# PAGE1.net
KiCad netlist of a schematic drawn in Altium Designer
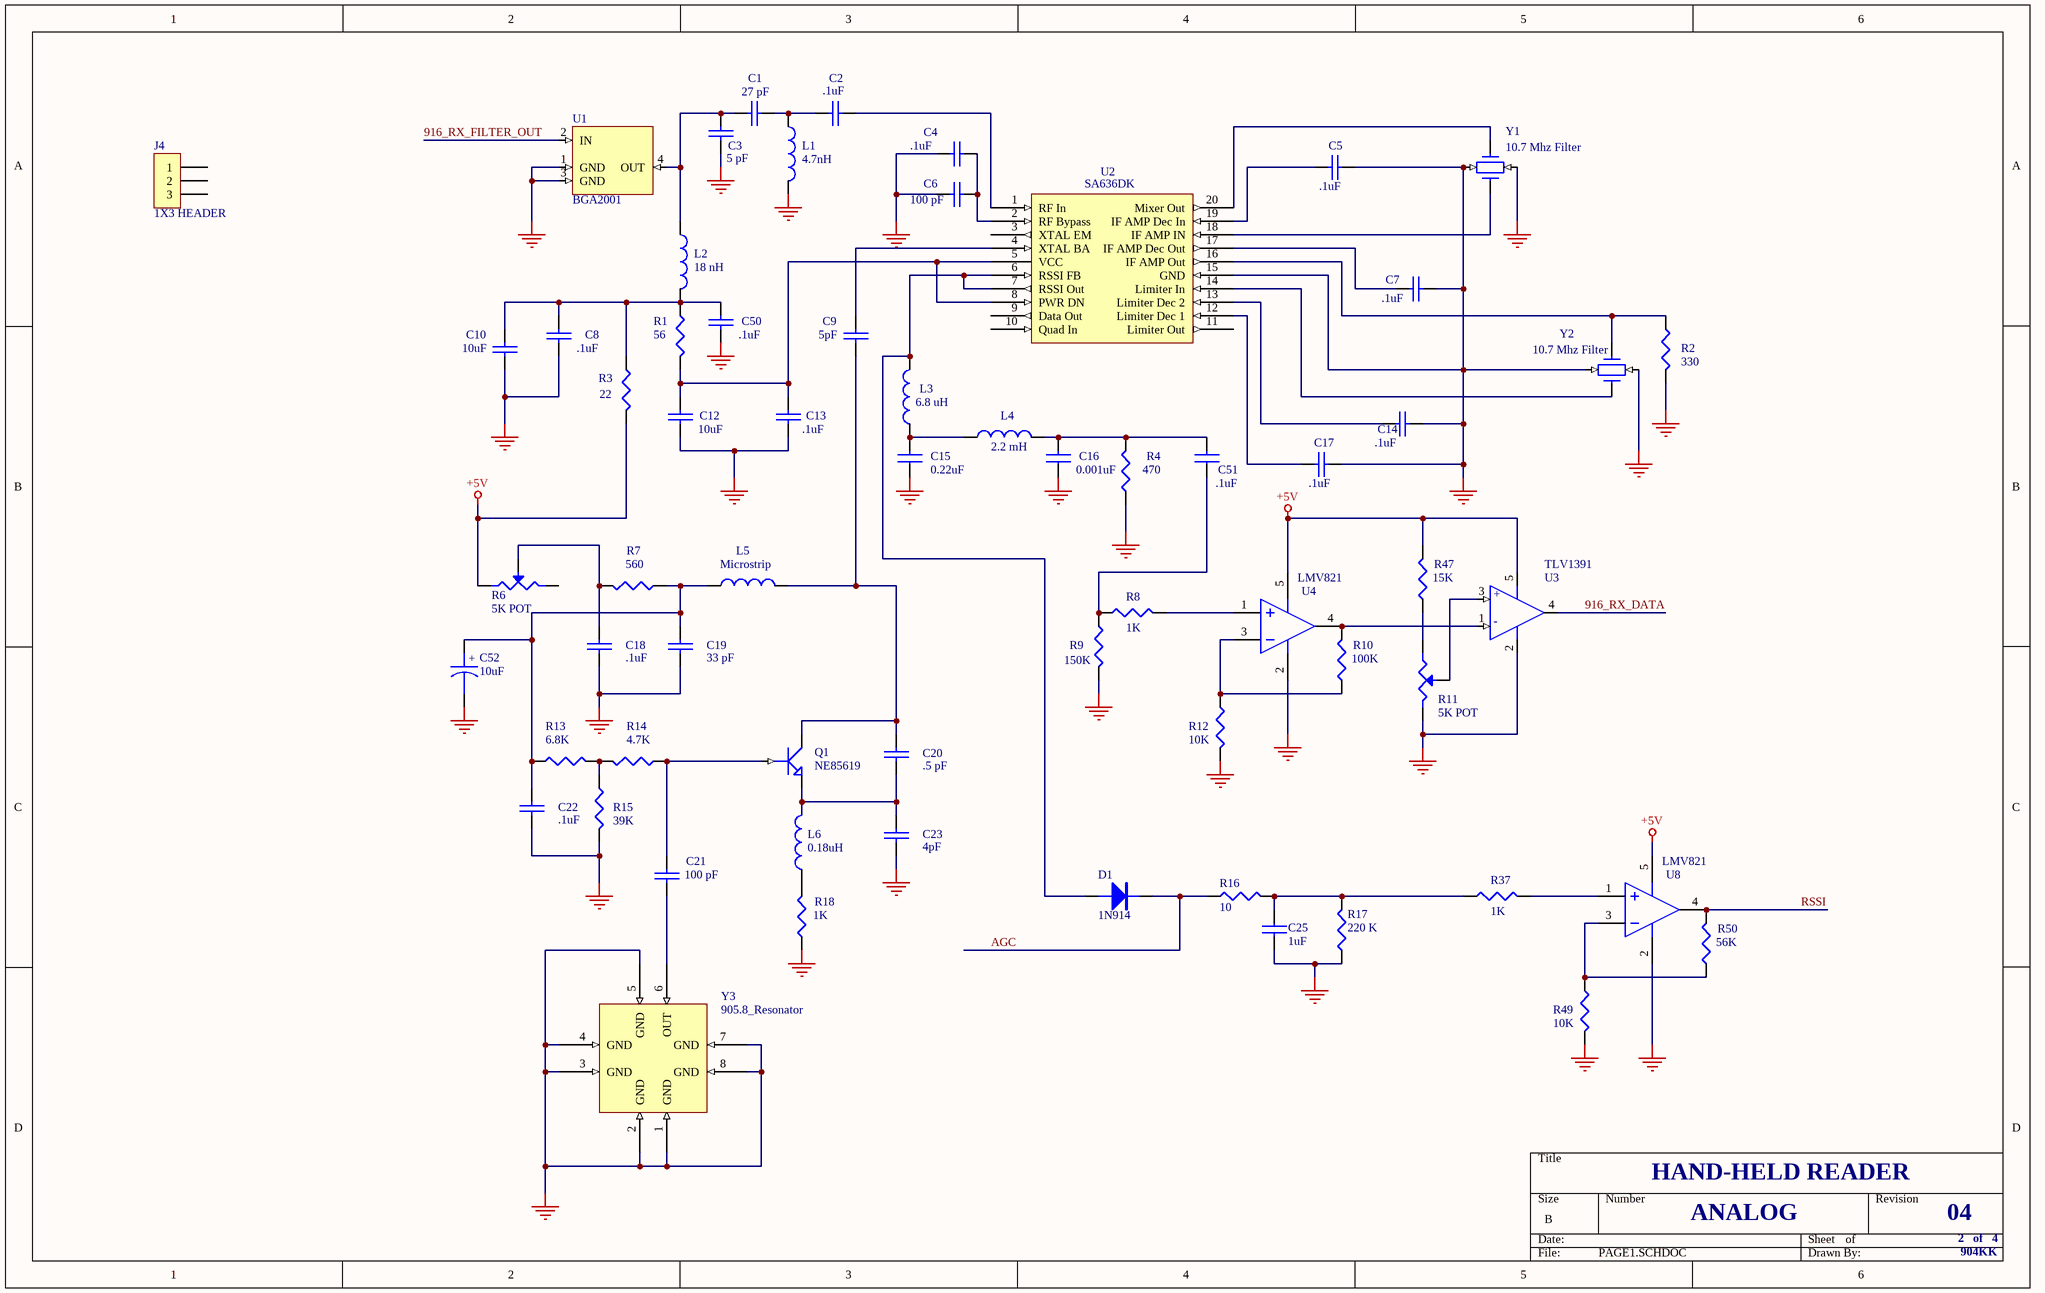
[diagram p0: PAGE1.SCHDOC]

(export (version "E")
  (design (tool "Eeschema 10.0.6"))
  (components
    (comp (ref "C1")
      (value "27 pF")
      (footprint "0603")
      (description "Capacitor")
      (libsource (lib "*") (part "CAP"))
    )
    (comp (ref "C2")
      (value ".1uF")
      (footprint "0603")
      (description "Capacitor")
      (libsource (lib "*") (part "CAP"))
    )
    (comp (ref "C3")
      (value "5 pF")
      (footprint "0603")
      (description "Capacitor")
      (libsource (lib "*") (part "CAP"))
    )
    (comp (ref "C4")
      (value ".1uF")
      (footprint "0603")
      (description "Capacitor")
      (libsource (lib "*") (part "CAP"))
    )
    (comp (ref "C5")
      (value ".1uF")
      (footprint "0603")
      (description "Capacitor")
      (libsource (lib "*") (part "CAP"))
    )
    (comp (ref "C6")
      (value "100 pF")
      (footprint "0603")
      (description "Capacitor")
      (libsource (lib "*") (part "CAP"))
    )
    (comp (ref "C7")
      (value ".1uF")
      (footprint "0603")
      (description "Capacitor")
      (libsource (lib "*") (part "CAP"))
    )
    (comp (ref "C8")
      (value ".1uF")
      (footprint "0603")
      (description "Capacitor")
      (libsource (lib "*") (part "CAP"))
    )
    (comp (ref "C9")
      (value "5pF")
      (footprint "0603")
      (description "Capacitor")
      (libsource (lib "*") (part "CAP"))
    )
    (comp (ref "C10")
      (value "10uF")
      (footprint "CAP A CASE")
      (description "Capacitor")
      (libsource (lib "*") (part "CAP"))
    )
    (comp (ref "C12")
      (value "10uF")
      (footprint "CAP A CASE")
      (description "Capacitor")
      (libsource (lib "*") (part "CAP"))
    )
    (comp (ref "C13")
      (value ".1uF")
      (footprint "0603")
      (description "Capacitor")
      (libsource (lib "*") (part "CAP"))
    )
    (comp (ref "C14")
      (value ".1uF")
      (footprint "0603")
      (description "Capacitor")
      (libsource (lib "*") (part "CAP"))
    )
    (comp (ref "C15") (value "0.22uF") (footprint "0603") (libsource (lib "*") (part "CAP_NP")))
    (comp (ref "C16") (value "0.001uF") (footprint "0603") (libsource (lib "*") (part "CAP_NP")))
    (comp (ref "C17")
      (value ".1uF")
      (footprint "0603")
      (description "Capacitor")
      (libsource (lib "*") (part "CAP"))
    )
    (comp (ref "C18")
      (value ".1uF")
      (footprint "0603")
      (description "Capacitor")
      (libsource (lib "*") (part "CAP"))
    )
    (comp (ref "C19")
      (value "33 pF")
      (footprint "0603")
      (description "Capacitor")
      (libsource (lib "*") (part "CAP"))
    )
    (comp (ref "C20")
      (value ".5 pF")
      (footprint "0603")
      (description "Capacitor")
      (libsource (lib "*") (part "CAP"))
    )
    (comp (ref "C21")
      (value "100 pF")
      (footprint "0603")
      (description "Capacitor")
      (libsource (lib "*") (part "CAP"))
    )
    (comp (ref "C22")
      (value ".1uF")
      (footprint "0603")
      (description "Capacitor")
      (libsource (lib "*") (part "CAP"))
    )
    (comp (ref "C23")
      (value "4pF")
      (footprint "0603")
      (description "Capacitor")
      (libsource (lib "*") (part "CAP"))
    )
    (comp (ref "C25") (value "1uF") (footprint "CAP A CASE") (libsource (lib "*") (part "CAP_NP")))
    (comp (ref "C50")
      (value ".1uF")
      (footprint "0603")
      (description "Capacitor")
      (libsource (lib "*") (part "CAP"))
    )
    (comp (ref "C51") (value ".1uF") (footprint "0603") (libsource (lib "*") (part "CAP_NP")))
    (comp (ref "C52")
      (value "10uF")
      (footprint "CAP A CASE")
      (description "Capacitor")
      (libsource (lib "*") (part "CAPACITOR POL"))
    )
    (comp (ref "D1")
      (value "1N914")
      (footprint "SOT23 DIODE")
      (description "Diode")
      (libsource (lib "*") (part "DIODE"))
    )
    (comp (ref "J4")
      (value "1X3 HEADER")
      (footprint "1X3 HEADER")
      (description "Connector")
      (libsource (lib "*") (part "CON3"))
    )
    (comp (ref "L1") (value "4.7nH") (footprint "0603") (libsource (lib "*") (part "INDUCTOR")))
    (comp (ref "L2") (value "18 nH") (footprint "0603") (libsource (lib "*") (part "INDUCTOR")))
    (comp (ref "L3") (value "6.8 uH") (footprint "0805") (libsource (lib "*") (part "INDUCTOR")))
    (comp (ref "L4") (value "2.2 mH") (footprint "COIL 6.8UH") (libsource (lib "*") (part "INDUCTOR")))
    (comp (ref "L5") (value "Microstrip") (footprint "MICROSTRIP") (libsource (lib "*") (part "INDUCTOR")))
    (comp (ref "L6") (value "0.18uH") (footprint "0603") (libsource (lib "*") (part "INDUCTOR")))
    (comp (ref "Q1")
      (value "NE85619")
      (footprint "3 PIN ULTRA SUPER MINI MOLD")
      (description "NPN Transistor")
      (libsource (lib "*") (part "NPN1"))
    )
    (comp (ref "R1") (value "56") (footprint "0603") (libsource (lib "*") (part "R")))
    (comp (ref "R2") (value "330") (footprint "0603") (libsource (lib "*") (part "R")))
    (comp (ref "R3") (value "22") (footprint "0603") (libsource (lib "*") (part "R")))
    (comp (ref "R4") (value "470") (footprint "0603") (libsource (lib "*") (part "R")))
    (comp (ref "R6")
      (value "5K POT")
      (footprint "POT PANA EVN5")
      (description "Potentiometer")
      (libsource (lib "*") (part "POT1"))
    )
    (comp (ref "R7") (value "560") (footprint "0603") (libsource (lib "*") (part "RESISTOR")))
    (comp (ref "R8") (value "1K") (footprint "0603") (libsource (lib "*") (part "R")))
    (comp (ref "R9") (value "150K") (footprint "0603") (libsource (lib "*") (part "R")))
    (comp (ref "R10") (value "100K") (footprint "0603") (libsource (lib "*") (part "R")))
    (comp (ref "R11")
      (value "5K POT")
      (footprint "POT PANA EVN5")
      (description "Potentiometer")
      (libsource (lib "*") (part "POT1"))
    )
    (comp (ref "R12") (value "10K") (footprint "0603") (libsource (lib "*") (part "R")))
    (comp (ref "R13") (value "6.8K") (footprint "0603") (libsource (lib "*") (part "RESISTOR")))
    (comp (ref "R14") (value "4.7K") (footprint "0603") (libsource (lib "*") (part "RESISTOR")))
    (comp (ref "R15") (value "39K") (footprint "0603") (libsource (lib "*") (part "RESISTOR")))
    (comp (ref "R16") (value "10") (footprint "0603") (libsource (lib "*") (part "R")))
    (comp (ref "R17") (value "220 K") (footprint "0603") (libsource (lib "*") (part "R")))
    (comp (ref "R18") (value "1K") (footprint "0603") (libsource (lib "*") (part "RESISTOR")))
    (comp (ref "R37") (value "1K") (footprint "0603") (libsource (lib "*") (part "R")))
    (comp (ref "R47") (value "15K") (footprint "0603") (libsource (lib "*") (part "R")))
    (comp (ref "R49") (value "10K") (footprint "0603") (libsource (lib "*") (part "R")))
    (comp (ref "R50") (value "56K") (footprint "0603") (libsource (lib "*") (part "R")))
    (comp (ref "U1") (value "BGA2001") (footprint "SOT343") (libsource (lib "*") (part "BGA2001")))
    (comp (ref "U2") (value "SA636DK") (footprint "SSOP20") (libsource (lib "*") (part "SA636DK")))
    (comp (ref "U3") (value "TLV1391") (footprint "SOT25") (libsource (lib "*") (part "TLV1391")))
    (comp (ref "U4") (value "LMV821") (footprint "SOT25") (libsource (lib "*") (part "OPAMP1")))
    (comp (ref "U8") (value "LMV821") (footprint "SOT25") (libsource (lib "*") (part "OPAMP1")))
    (comp (ref "Y1") (value "10.7 Mhz Filter") (footprint "FILTER") (libsource (lib "*") (part "FILTER")))
    (comp (ref "Y2") (value "10.7 Mhz Filter") (footprint "FILTER") (libsource (lib "*") (part "FILTER")))
    (comp (ref "Y3")
      (value "905.8_Resonator")
      (footprint "RESONATOR")
      (libsource (lib "*") (part "RESONATOR"))
    )
  )
  (nets
    (net (code "1") (name "+5V") (class "Default")
      (node (ref "R3") (pin "2") (pinfunction "2_2") (pintype "passive"))
      (node (ref "R47") (pin "2") (pinfunction "2_2") (pintype "passive"))
      (node (ref "R6") (pin "1") (pinfunction "1_1") (pintype "passive"))
      (node (ref "U3") (pin "5") (pinfunction "VDD_5") (pintype "power_in"))
      (node (ref "U4") (pin "5") (pinfunction "5_5") (pintype "passive"))
      (node (ref "U8") (pin "5") (pinfunction "5_5") (pintype "passive"))
    )
    (net (code "2") (name "/916_RX_DATA") (class "Default")
      (node (ref "U3") (pin "4") (pinfunction "OUT_4") (pintype "open_collector"))
    )
    (net (code "3") (name "/916_RX_FILTER_OUT") (class "Default")
      (node (ref "U1") (pin "2") (pinfunction "IN_2") (pintype "input"))
    )
    (net (code "4") (name "/AGC") (class "Default")
      (node (ref "D1") (pin "K") (pinfunction "K_K") (pintype "passive"))
      (node (ref "R16") (pin "2") (pinfunction "2_2") (pintype "passive"))
    )
    (net (code "5") (name "/RSSI") (class "Default")
      (node (ref "R50") (pin "2") (pinfunction "2_2") (pintype "passive"))
      (node (ref "U8") (pin "4") (pinfunction "4_4") (pintype "passive"))
    )
    (net (code "6") (name "GND_SIGNAL") (class "Default")
      (node (ref "C10") (pin "2") (pinfunction "2_2") (pintype "passive"))
      (node (ref "C12") (pin "2") (pinfunction "2_2") (pintype "passive"))
      (node (ref "C13") (pin "2") (pinfunction "2_2") (pintype "passive"))
      (node (ref "C14") (pin "2") (pinfunction "2_2") (pintype "passive"))
      (node (ref "C15") (pin "1") (pinfunction "1_1") (pintype "passive"))
      (node (ref "C16") (pin "1") (pinfunction "1_1") (pintype "passive"))
      (node (ref "C17") (pin "2") (pinfunction "2_2") (pintype "passive"))
      (node (ref "C18") (pin "2") (pinfunction "2_2") (pintype "passive"))
      (node (ref "C19") (pin "2") (pinfunction "2_2") (pintype "passive"))
      (node (ref "C22") (pin "2") (pinfunction "2_2") (pintype "passive"))
      (node (ref "C23") (pin "2") (pinfunction "2_2") (pintype "passive"))
      (node (ref "C25") (pin "2") (pinfunction "2_2") (pintype "passive"))
      (node (ref "C3") (pin "2") (pinfunction "2_2") (pintype "passive"))
      (node (ref "C4") (pin "1") (pinfunction "1_1") (pintype "passive"))
      (node (ref "C5") (pin "2") (pinfunction "2_2") (pintype "passive"))
      (node (ref "C50") (pin "2") (pinfunction "2_2") (pintype "passive"))
      (node (ref "C52") (pin "2") (pinfunction "2_2") (pintype "passive"))
      (node (ref "C6") (pin "1") (pinfunction "1_1") (pintype "passive"))
      (node (ref "C7") (pin "2") (pinfunction "2_2") (pintype "passive"))
      (node (ref "C8") (pin "2") (pinfunction "2_2") (pintype "passive"))
      (node (ref "L1") (pin "2") (pinfunction "2_2") (pintype "passive"))
      (node (ref "R11") (pin "3") (pinfunction "3_3") (pintype "passive"))
      (node (ref "R12") (pin "2") (pinfunction "2_2") (pintype "passive"))
      (node (ref "R15") (pin "2") (pinfunction "2_2") (pintype "passive"))
      (node (ref "R17") (pin "2") (pinfunction "2_2") (pintype "passive"))
      (node (ref "R18") (pin "1") (pinfunction "1_1") (pintype "passive"))
      (node (ref "R2") (pin "2") (pinfunction "2_2") (pintype "passive"))
      (node (ref "R4") (pin "1") (pinfunction "1_1") (pintype "passive"))
      (node (ref "R49") (pin "2") (pinfunction "2_2") (pintype "passive"))
      (node (ref "R9") (pin "2") (pinfunction "2_2") (pintype "passive"))
      (node (ref "U1") (pin "1") (pinfunction "GND_1") (pintype "input"))
      (node (ref "U1") (pin "3") (pinfunction "GND_3") (pintype "input"))
      (node (ref "U2") (pin "15") (pinfunction "GND_15") (pintype "input"))
      (node (ref "U3") (pin "2") (pinfunction "VSS_2") (pintype "power_in"))
      (node (ref "U4") (pin "2") (pinfunction "2_2") (pintype "passive"))
      (node (ref "U8") (pin "2") (pinfunction "2_2") (pintype "passive"))
      (node (ref "Y1") (pin "2") (pinfunction "2_2") (pintype "input"))
      (node (ref "Y2") (pin "2") (pinfunction "2_2") (pintype "input"))
      (node (ref "Y3") (pin "1") (pinfunction "GND_1") (pintype "input"))
      (node (ref "Y3") (pin "2") (pinfunction "GND_2") (pintype "input"))
      (node (ref "Y3") (pin "3") (pinfunction "GND_3") (pintype "input"))
      (node (ref "Y3") (pin "4") (pinfunction "GND_4") (pintype "input"))
      (node (ref "Y3") (pin "5") (pinfunction "GND_5") (pintype "input"))
      (node (ref "Y3") (pin "7") (pinfunction "GND_7") (pintype "input"))
      (node (ref "Y3") (pin "8") (pinfunction "GND_8") (pintype "input"))
    )
    (net (code "7") (name "Net-(C1-Pad2)") (class "Default")
      (node (ref "C1") (pin "2") (pinfunction "2_2") (pintype "passive"))
      (node (ref "C2") (pin "1") (pinfunction "1_1") (pintype "passive"))
      (node (ref "L1") (pin "1") (pinfunction "1_1") (pintype "passive"))
    )
    (net (code "8") (name "Net-(C10-Pad1)") (class "Default")
      (node (ref "C10") (pin "1") (pinfunction "1_1") (pintype "passive"))
      (node (ref "C50") (pin "1") (pinfunction "1_1") (pintype "passive"))
      (node (ref "C8") (pin "1") (pinfunction "1_1") (pintype "passive"))
      (node (ref "L2") (pin "2") (pinfunction "2_2") (pintype "passive"))
      (node (ref "R1") (pin "1") (pinfunction "1_1") (pintype "passive"))
      (node (ref "R3") (pin "1") (pinfunction "1_1") (pintype "passive"))
    )
    (net (code "9") (name "Net-(C15-Pad2)") (class "Default")
      (node (ref "C15") (pin "2") (pinfunction "2_2") (pintype "passive"))
      (node (ref "L3") (pin "1") (pinfunction "1_1") (pintype "passive"))
      (node (ref "L4") (pin "1") (pinfunction "1_1") (pintype "passive"))
    )
    (net (code "10") (name "Net-(C16-Pad2)") (class "Default")
      (node (ref "C16") (pin "2") (pinfunction "2_2") (pintype "passive"))
      (node (ref "C51") (pin "2") (pinfunction "2_2") (pintype "passive"))
      (node (ref "L4") (pin "2") (pinfunction "2_2") (pintype "passive"))
      (node (ref "R4") (pin "2") (pinfunction "2_2") (pintype "passive"))
    )
    (net (code "11") (name "Net-(C18-Pad1)") (class "Default")
      (node (ref "C18") (pin "1") (pinfunction "1_1") (pintype "passive"))
      (node (ref "R6") (pin "2") (pinfunction "2_2") (pintype "passive"))
      (node (ref "R7") (pin "2") (pinfunction "2_2") (pintype "passive"))
    )
    (net (code "12") (name "Net-(C19-Pad1)") (class "Default")
      (node (ref "C19") (pin "1") (pinfunction "1_1") (pintype "passive"))
      (node (ref "C22") (pin "1") (pinfunction "1_1") (pintype "passive"))
      (node (ref "C52") (pin "1") (pinfunction "1_1") (pintype "passive"))
      (node (ref "L5") (pin "1") (pinfunction "1_1") (pintype "passive"))
      (node (ref "R13") (pin "1") (pinfunction "1_1") (pintype "passive"))
      (node (ref "R7") (pin "1") (pinfunction "1_1") (pintype "passive"))
    )
    (net (code "13") (name "Net-(C20-Pad1)") (class "Default")
      (node (ref "C20") (pin "1") (pinfunction "1_1") (pintype "passive"))
      (node (ref "C9") (pin "1") (pinfunction "1_1") (pintype "passive"))
      (node (ref "L5") (pin "2") (pinfunction "2_2") (pintype "passive"))
      (node (ref "Q1") (pin "C") (pinfunction "C_C") (pintype "passive"))
    )
    (net (code "14") (name "Net-(C20-Pad2)") (class "Default")
      (node (ref "C20") (pin "2") (pinfunction "2_2") (pintype "passive"))
      (node (ref "C23") (pin "1") (pinfunction "1_1") (pintype "passive"))
      (node (ref "L6") (pin "2") (pinfunction "2_2") (pintype "passive"))
      (node (ref "Q1") (pin "E") (pinfunction "E_E") (pintype "passive"))
    )
    (net (code "15") (name "Net-(C21-Pad1)") (class "Default")
      (node (ref "C21") (pin "1") (pinfunction "1_1") (pintype "passive"))
      (node (ref "Q1") (pin "B") (pinfunction "B_B") (pintype "input"))
      (node (ref "R14") (pin "1") (pinfunction "1_1") (pintype "passive"))
    )
    (net (code "16") (name "Net-(C25-Pad1)") (class "Default")
      (node (ref "C25") (pin "1") (pinfunction "1_1") (pintype "passive"))
      (node (ref "R16") (pin "1") (pinfunction "1_1") (pintype "passive"))
      (node (ref "R17") (pin "1") (pinfunction "1_1") (pintype "passive"))
      (node (ref "R37") (pin "1") (pinfunction "1_1") (pintype "passive"))
    )
    (net (code "17") (name "Net-(C51-Pad1)") (class "Default")
      (node (ref "C51") (pin "1") (pinfunction "1_1") (pintype "passive"))
      (node (ref "R8") (pin "1") (pinfunction "1_1") (pintype "passive"))
      (node (ref "R9") (pin "1") (pinfunction "1_1") (pintype "passive"))
    )
    (net (code "18") (name "Net-(L6-Pad1)") (class "Default")
      (node (ref "L6") (pin "1") (pinfunction "1_1") (pintype "passive"))
      (node (ref "R18") (pin "2") (pinfunction "2_2") (pintype "passive"))
    )
    (net (code "19") (name "Net-(R8-Pad2)") (class "Default")
      (node (ref "R8") (pin "2") (pinfunction "2_2") (pintype "passive"))
      (node (ref "U4") (pin "1") (pinfunction "1_1") (pintype "passive"))
    )
    (net (code "20") (name "Net-(R10-Pad1)") (class "Default")
      (node (ref "R10") (pin "1") (pinfunction "1_1") (pintype "passive"))
      (node (ref "R12") (pin "1") (pinfunction "1_1") (pintype "passive"))
      (node (ref "U4") (pin "3") (pinfunction "3_3") (pintype "passive"))
    )
    (net (code "21") (name "Net-(R11-Pad1)") (class "Default")
      (node (ref "R11") (pin "1") (pinfunction "1_1") (pintype "passive"))
      (node (ref "R47") (pin "1") (pinfunction "1_1") (pintype "passive"))
    )
    (net (code "22") (name "Net-(R13-Pad2)") (class "Default")
      (node (ref "R13") (pin "2") (pinfunction "2_2") (pintype "passive"))
      (node (ref "R14") (pin "2") (pinfunction "2_2") (pintype "passive"))
      (node (ref "R15") (pin "1") (pinfunction "1_1") (pintype "passive"))
    )
    (net (code "23") (name "Net-(R37-Pad2)") (class "Default")
      (node (ref "R37") (pin "2") (pinfunction "2_2") (pintype "passive"))
      (node (ref "U8") (pin "1") (pinfunction "1_1") (pintype "passive"))
    )
    (net (code "24") (name "Net-(R49-Pad1)") (class "Default")
      (node (ref "R49") (pin "1") (pinfunction "1_1") (pintype "passive"))
      (node (ref "R50") (pin "1") (pinfunction "1_1") (pintype "passive"))
      (node (ref "U8") (pin "3") (pinfunction "3_3") (pintype "passive"))
    )
    (net (code "25") (name "Net-(U1-OUT)") (class "Default")
      (node (ref "C1") (pin "1") (pinfunction "1_1") (pintype "passive"))
      (node (ref "C3") (pin "1") (pinfunction "1_1") (pintype "passive"))
      (node (ref "L2") (pin "1") (pinfunction "1_1") (pintype "passive"))
      (node (ref "U1") (pin "4") (pinfunction "OUT_4") (pintype "input"))
    )
    (net (code "26") (name "Net-(U2-IF_AMP_Dec_In)") (class "Default")
      (node (ref "C5") (pin "1") (pinfunction "1_1") (pintype "passive"))
      (node (ref "U2") (pin "19") (pinfunction "IF_AMP_Dec_In_19") (pintype "input"))
    )
    (net (code "27") (name "Net-(U2-IF_AMP_Dec_Out)") (class "Default")
      (node (ref "C7") (pin "1") (pinfunction "1_1") (pintype "passive"))
      (node (ref "U2") (pin "17") (pinfunction "IF_AMP_Dec_Out_17") (pintype "output"))
    )
    (net (code "28") (name "Net-(U2-IF_AMP_IN)") (class "Default")
      (node (ref "U2") (pin "18") (pinfunction "IF_AMP_IN_18") (pintype "input"))
      (node (ref "Y1") (pin "3") (pinfunction "3_3") (pintype "passive"))
    )
    (net (code "29") (name "Net-(U2-IF_AMP_Out)") (class "Default")
      (node (ref "R2") (pin "1") (pinfunction "1_1") (pintype "passive"))
      (node (ref "U2") (pin "16") (pinfunction "IF_AMP_Out_16") (pintype "output"))
      (node (ref "Y2") (pin "1") (pinfunction "1_1") (pintype "passive"))
    )
    (net (code "30") (name "Net-(U2-Limiter_Dec_1)") (class "Default")
      (node (ref "C17") (pin "1") (pinfunction "1_1") (pintype "passive"))
      (node (ref "U2") (pin "12") (pinfunction "Limiter_Dec_1_12") (pintype "input"))
    )
    (net (code "31") (name "Net-(U2-Limiter_Dec_2)") (class "Default")
      (node (ref "C14") (pin "1") (pinfunction "1_1") (pintype "passive"))
      (node (ref "U2") (pin "13") (pinfunction "Limiter_Dec_2_13") (pintype "input"))
    )
    (net (code "32") (name "Net-(U2-Limiter_In)") (class "Default")
      (node (ref "U2") (pin "14") (pinfunction "Limiter_In_14") (pintype "input"))
      (node (ref "Y2") (pin "3") (pinfunction "3_3") (pintype "passive"))
    )
    (net (code "33") (name "Net-(U2-Mixer_Out)") (class "Default")
      (node (ref "U2") (pin "20") (pinfunction "Mixer_Out_20") (pintype "output"))
      (node (ref "Y1") (pin "1") (pinfunction "1_1") (pintype "passive"))
    )
    (net (code "34") (name "Net-(U2-PWR_DN)") (class "Default")
      (node (ref "C12") (pin "1") (pinfunction "1_1") (pintype "passive"))
      (node (ref "C13") (pin "1") (pinfunction "1_1") (pintype "passive"))
      (node (ref "R1") (pin "2") (pinfunction "2_2") (pintype "passive"))
      (node (ref "U2") (pin "5") (pinfunction "VCC_5") (pintype "power_in"))
      (node (ref "U2") (pin "8") (pinfunction "PWR_DN_8") (pintype "input"))
    )
    (net (code "35") (name "Net-(U2-RF_Bypass)") (class "Default")
      (node (ref "C4") (pin "2") (pinfunction "2_2") (pintype "passive"))
      (node (ref "C6") (pin "2") (pinfunction "2_2") (pintype "passive"))
      (node (ref "U2") (pin "2") (pinfunction "RF_Bypass_2") (pintype "input"))
    )
    (net (code "36") (name "Net-(U2-RF_In)") (class "Default")
      (node (ref "C2") (pin "2") (pinfunction "2_2") (pintype "passive"))
      (node (ref "U2") (pin "1") (pinfunction "RF_In_1") (pintype "input"))
    )
    (net (code "37") (name "Net-(U2-RSSI_FB)") (class "Default")
      (node (ref "D1") (pin "A") (pinfunction "A_A") (pintype "passive"))
      (node (ref "L3") (pin "2") (pinfunction "2_2") (pintype "passive"))
      (node (ref "U2") (pin "6") (pinfunction "RSSI_FB_6") (pintype "input"))
      (node (ref "U2") (pin "7") (pinfunction "RSSI_Out_7") (pintype "output"))
    )
    (net (code "38") (name "Net-(U2-XTAL_BA)") (class "Default")
      (node (ref "C9") (pin "2") (pinfunction "2_2") (pintype "passive"))
      (node (ref "U2") (pin "4") (pinfunction "XTAL_BA_4") (pintype "input"))
    )
    (net (code "39") (name "Net-(U3-+)") (class "Default")
      (node (ref "R11") (pin "2") (pinfunction "2_2") (pintype "passive"))
      (node (ref "U3") (pin "3") (pinfunction "+_3") (pintype "input"))
    )
    (net (code "40") (name "Net-(U3--)") (class "Default")
      (node (ref "R10") (pin "2") (pinfunction "2_2") (pintype "passive"))
      (node (ref "U3") (pin "1") (pinfunction "-_1") (pintype "input"))
      (node (ref "U4") (pin "4") (pinfunction "4_4") (pintype "passive"))
    )
    (net (code "41") (name "Net-(Y3-OUT)") (class "Default")
      (node (ref "C21") (pin "2") (pinfunction "2_2") (pintype "passive"))
      (node (ref "Y3") (pin "6") (pinfunction "OUT_6") (pintype "input"))
    )
    (net (code "42") (name "unconnected-(J4-Pad1)") (class "Default")
      (node (ref "J4") (pin "1") (pinfunction "1_1") (pintype "passive"))
    )
    (net (code "43") (name "unconnected-(J4-Pad2)") (class "Default")
      (node (ref "J4") (pin "2") (pinfunction "2_2") (pintype "passive"))
    )
    (net (code "44") (name "unconnected-(J4-Pad3)") (class "Default")
      (node (ref "J4") (pin "3") (pinfunction "3_3") (pintype "passive"))
    )
    (net (code "45") (name "unconnected-(R6-Pad3)") (class "Default")
      (node (ref "R6") (pin "3") (pinfunction "3_3") (pintype "passive"))
    )
    (net (code "46") (name "unconnected-(U2-Data_Out-Pad9)") (class "Default")
      (node (ref "U2") (pin "9") (pinfunction "Data_Out_9") (pintype "output"))
    )
    (net (code "47") (name "unconnected-(U2-Limiter_Out-Pad11)") (class "Default")
      (node (ref "U2") (pin "11") (pinfunction "Limiter_Out_11") (pintype "output"))
    )
    (net (code "48") (name "unconnected-(U2-Quad_In-Pad10)") (class "Default")
      (node (ref "U2") (pin "10") (pinfunction "Quad_In_10") (pintype "input"))
    )
    (net (code "49") (name "unconnected-(U2-XTAL_EM-Pad3)") (class "Default")
      (node (ref "U2") (pin "3") (pinfunction "XTAL_EM_3") (pintype "output"))
    )
  )
)
